# Ghidorah5_v2.net
KiCad netlist of a schematic drawn in EAGLE
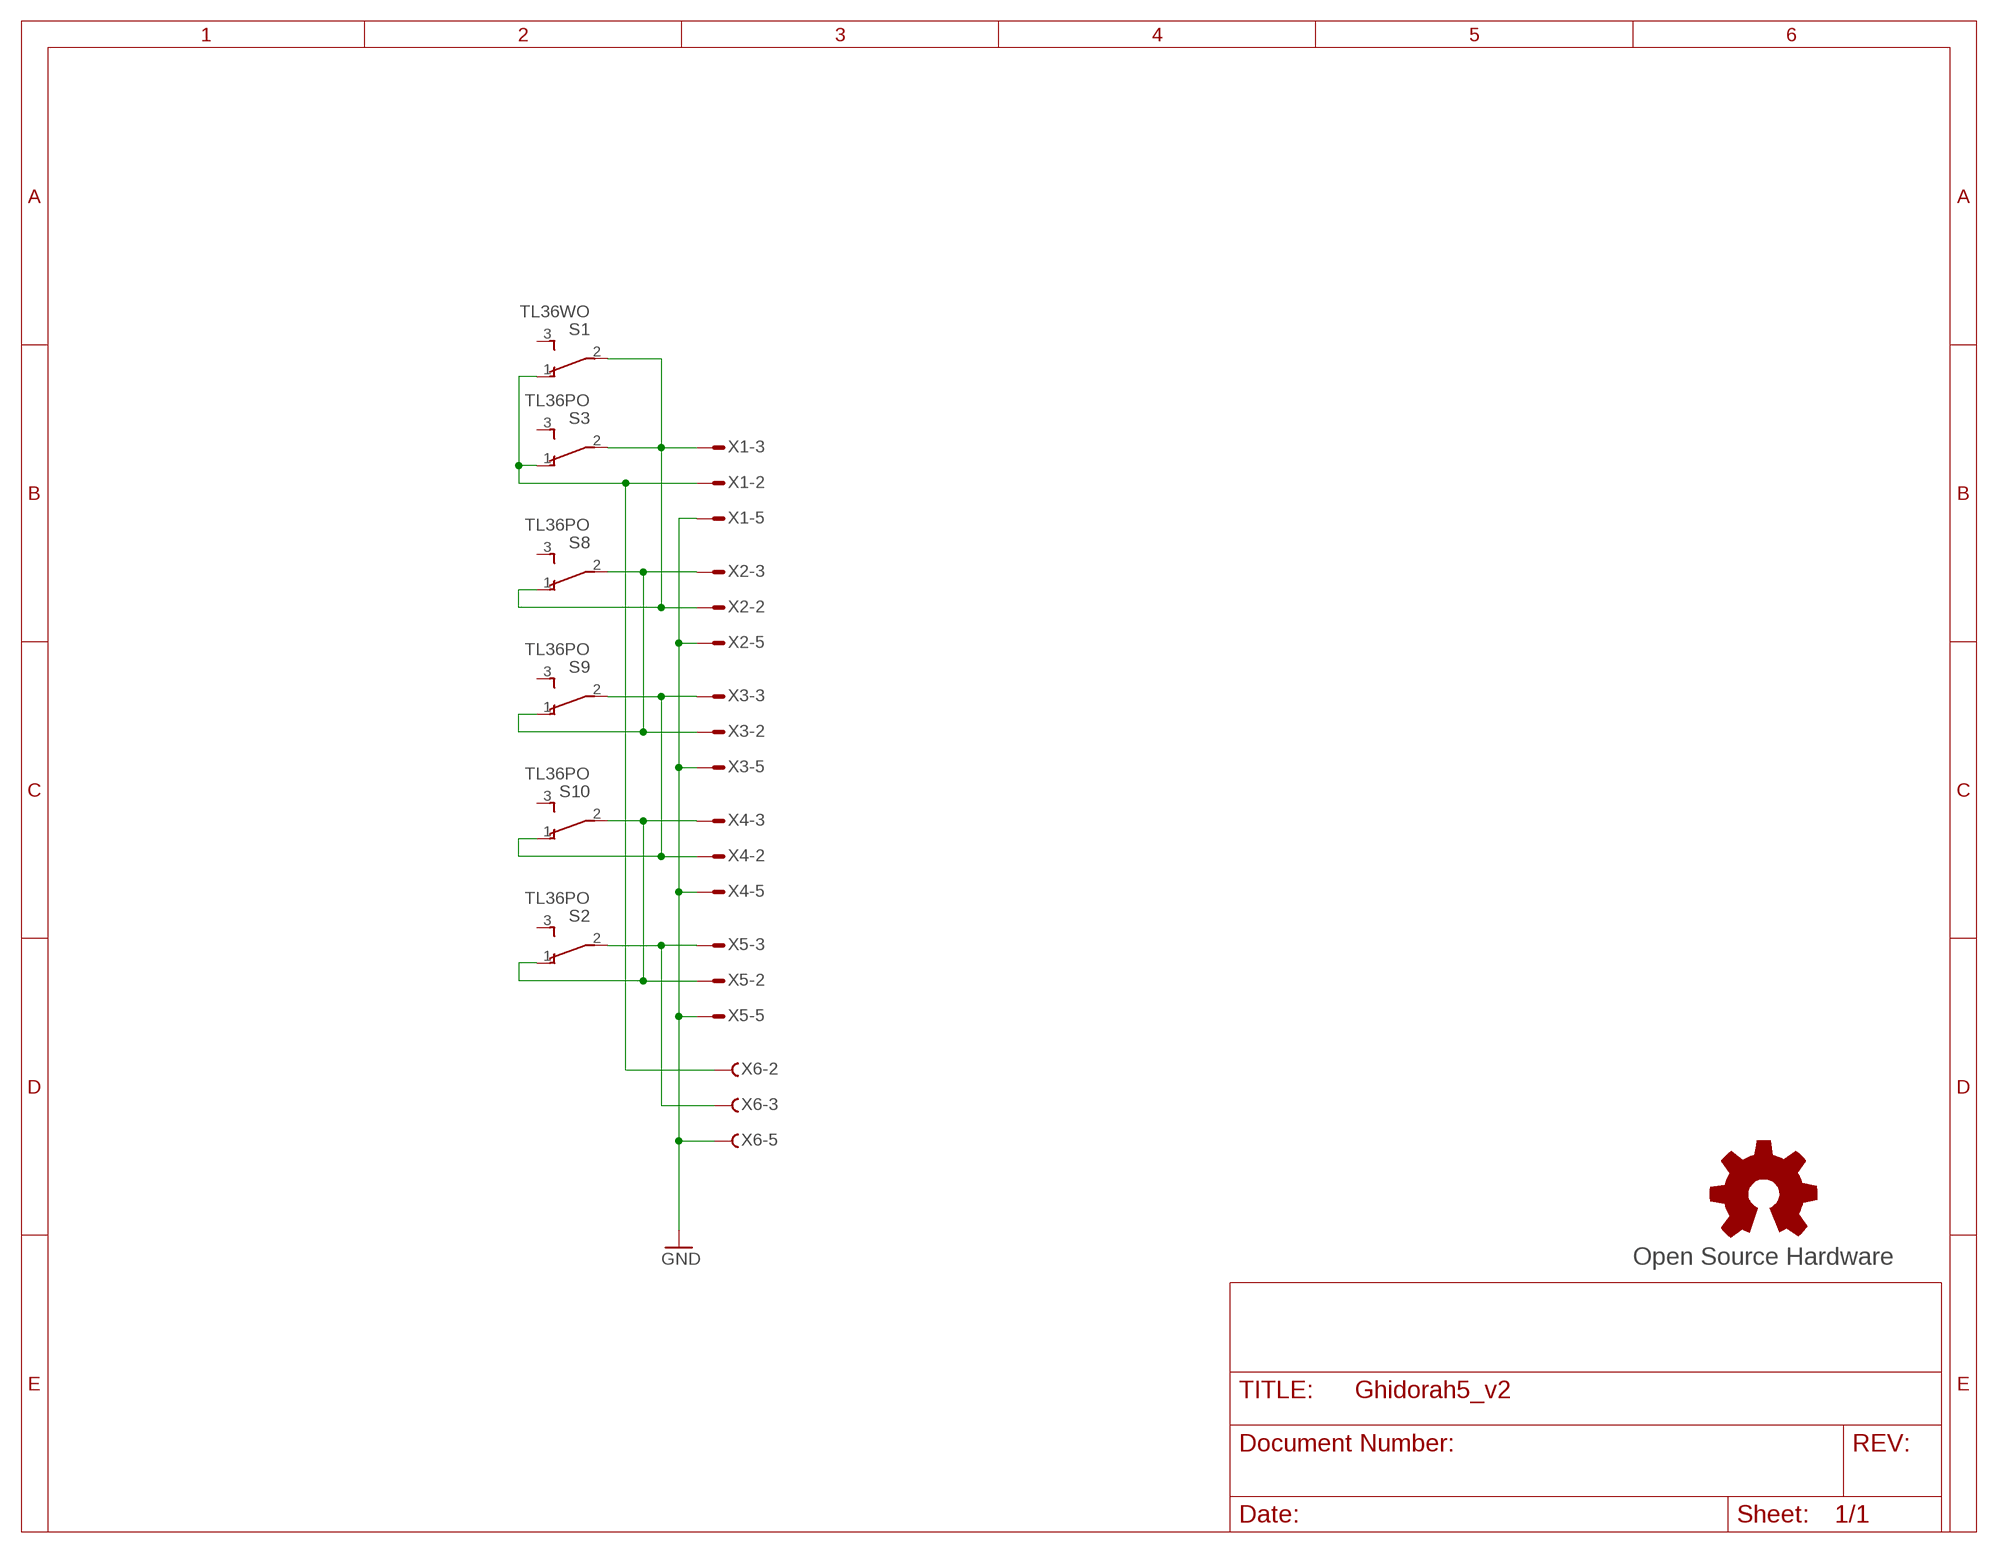
[diagram p0: schematic, sheet 1]

(export (version "E")
  (design (tool "Eeschema 10.0.6"))
  (components
    (comp (ref "GOLD_ORB_SM1")
      (value "Open Source Hardware")
      (footprint "eagle-import:OSHW_5MM")
      (libsource (lib "eagle-import") (part "OSHWLOGOLOGO5MM"))
    )
    (comp (ref "S1")
      (value "TL36WO")
      (footprint "eagle-import:TL3XWO")
      (libsource (lib "eagle-import") (part "TL36WO"))
    )
    (comp (ref "S2")
      (value "TL36PO")
      (footprint "eagle-import:TL3XPO")
      (libsource (lib "eagle-import") (part "TL36PO"))
    )
    (comp (ref "S3")
      (value "TL36PO")
      (footprint "eagle-import:TL3XPO")
      (libsource (lib "eagle-import") (part "TL36PO"))
    )
    (comp (ref "S8")
      (value "TL36PO")
      (footprint "eagle-import:TL3XPO")
      (libsource (lib "eagle-import") (part "TL36PO"))
    )
    (comp (ref "S9")
      (value "TL36PO")
      (footprint "eagle-import:TL3XPO")
      (libsource (lib "eagle-import") (part "TL36PO"))
    )
    (comp (ref "S10")
      (value "TL36PO")
      (footprint "eagle-import:TL3XPO")
      (libsource (lib "eagle-import") (part "TL36PO"))
    )
    (comp (ref "X1")
      (value "M09DS")
      (footprint "eagle-import:M09D")
      (libsource (lib "eagle-import") (part "M09?SD"))
    )
    (comp (ref "X2")
      (value "M09VS")
      (footprint "eagle-import:M09V")
      (libsource (lib "eagle-import") (part "M09?SV"))
    )
    (comp (ref "X3")
      (value "M09VS")
      (footprint "eagle-import:M09V")
      (libsource (lib "eagle-import") (part "M09?SV"))
    )
    (comp (ref "X4")
      (value "M09VS")
      (footprint "eagle-import:M09V")
      (libsource (lib "eagle-import") (part "M09?SV"))
    )
    (comp (ref "X5")
      (value "M09VS")
      (footprint "eagle-import:M09V")
      (libsource (lib "eagle-import") (part "M09?SV"))
    )
    (comp (ref "X6")
      (value "F09DS")
      (footprint "eagle-import:F09D")
      (libsource (lib "eagle-import") (part "F09?SD"))
    )
  )
  (nets
    (net (code "1") (name "GND") (class "Default")
      (node (ref "X1") (pin "5") (pinfunction "M_5") (pintype "passive"))
      (node (ref "X2") (pin "5") (pinfunction "M_5") (pintype "passive"))
      (node (ref "X3") (pin "5") (pinfunction "M_5") (pintype "passive"))
      (node (ref "X4") (pin "5") (pinfunction "M_5") (pintype "passive"))
      (node (ref "X5") (pin "5") (pinfunction "M_5") (pintype "passive"))
      (node (ref "X6") (pin "5") (pinfunction "F_5") (pintype "passive"))
    )
    (net (code "2") (name "Net-(S1-O)") (class "Default")
      (node (ref "S1") (pin "1") (pinfunction "O_1") (pintype "passive"))
      (node (ref "S3") (pin "1") (pinfunction "O_1") (pintype "passive"))
      (node (ref "X1") (pin "2") (pinfunction "M_2") (pintype "passive"))
      (node (ref "X6") (pin "2") (pinfunction "F_2") (pintype "passive"))
    )
    (net (code "3") (name "Net-(S1-P)") (class "Default")
      (node (ref "S1") (pin "2") (pinfunction "P_2") (pintype "passive"))
      (node (ref "S3") (pin "2") (pinfunction "P_2") (pintype "passive"))
      (node (ref "S8") (pin "1") (pinfunction "O_1") (pintype "passive"))
      (node (ref "X1") (pin "3") (pinfunction "M_3") (pintype "passive"))
      (node (ref "X2") (pin "2") (pinfunction "M_2") (pintype "passive"))
    )
    (net (code "4") (name "Net-(S2-P)") (class "Default")
      (node (ref "S2") (pin "2") (pinfunction "P_2") (pintype "passive"))
      (node (ref "X5") (pin "3") (pinfunction "M_3") (pintype "passive"))
      (node (ref "X6") (pin "3") (pinfunction "F_3") (pintype "passive"))
    )
    (net (code "5") (name "Net-(S8-P)") (class "Default")
      (node (ref "S8") (pin "2") (pinfunction "P_2") (pintype "passive"))
      (node (ref "S9") (pin "1") (pinfunction "O_1") (pintype "passive"))
      (node (ref "X2") (pin "3") (pinfunction "M_3") (pintype "passive"))
      (node (ref "X3") (pin "2") (pinfunction "M_2") (pintype "passive"))
    )
    (net (code "6") (name "Net-(S10-O)") (class "Default")
      (node (ref "S10") (pin "1") (pinfunction "O_1") (pintype "passive"))
      (node (ref "S9") (pin "2") (pinfunction "P_2") (pintype "passive"))
      (node (ref "X3") (pin "3") (pinfunction "M_3") (pintype "passive"))
      (node (ref "X4") (pin "2") (pinfunction "M_2") (pintype "passive"))
    )
    (net (code "7") (name "Net-(S10-P)") (class "Default")
      (node (ref "S10") (pin "2") (pinfunction "P_2") (pintype "passive"))
      (node (ref "S2") (pin "1") (pinfunction "O_1") (pintype "passive"))
      (node (ref "X4") (pin "3") (pinfunction "M_3") (pintype "passive"))
      (node (ref "X5") (pin "2") (pinfunction "M_2") (pintype "passive"))
    )
    (net (code "8") (name "unconnected-(S1-S-Pad3)") (class "Default")
      (node (ref "S1") (pin "3") (pinfunction "S_3") (pintype "passive"))
    )
    (net (code "9") (name "unconnected-(S2-S-Pad3)") (class "Default")
      (node (ref "S2") (pin "3") (pinfunction "S_3") (pintype "passive"))
    )
    (net (code "10") (name "unconnected-(S3-S-Pad3)") (class "Default")
      (node (ref "S3") (pin "3") (pinfunction "S_3") (pintype "passive"))
    )
    (net (code "11") (name "unconnected-(S8-S-Pad3)") (class "Default")
      (node (ref "S8") (pin "3") (pinfunction "S_3") (pintype "passive"))
    )
    (net (code "12") (name "unconnected-(S9-S-Pad3)") (class "Default")
      (node (ref "S9") (pin "3") (pinfunction "S_3") (pintype "passive"))
    )
    (net (code "13") (name "unconnected-(S10-S-Pad3)") (class "Default")
      (node (ref "S10") (pin "3") (pinfunction "S_3") (pintype "passive"))
    )
  )
)
